# 18-Power-P3V3.net
KiCad netlist of a schematic drawn in Altium Designer
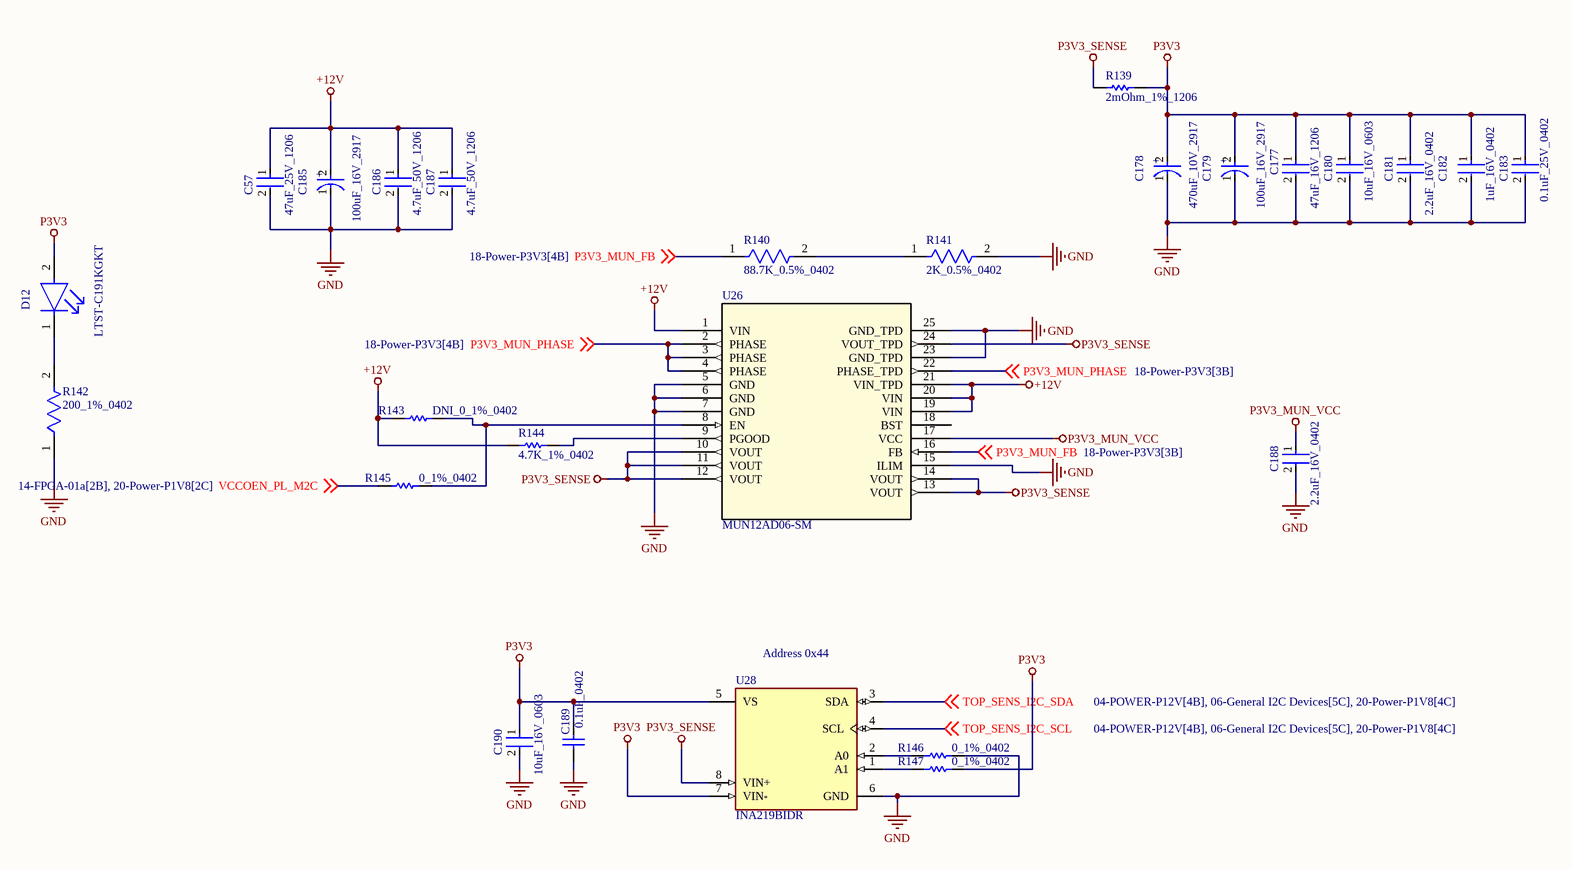
[diagram p0: 18-Power-P3V3.SchDoc]

(export (version "E")
  (design (tool "Eeschema 10.0.6"))
  (components
    (comp (ref "C57")
      (value "47uF_25V_1206")
      (footprint "FP-C3216-160-0_2-MFG")
      (description "Multilayer Ceramic Capacitors 47uF ±20% 25V X5R SMD 1206")
      (fields (field (name "VOLTAGE") "25V") (field (name "TOLERANCE") "20%"))
      (libsource (lib "Altium Content Vault") (part "11868f565c42a9108669ba33697ecf6"))
    )
    (comp (ref "C177")
      (value "47uF_16V_1206")
      (footprint "FP-C3216-160-0_2-MFG")
      (description "Multilayer Ceramic Capacitors 47uF ±20% 16V X5R SMD 1206")
      (fields (field (name "TOLERANCE") "20%"))
      (libsource (lib "Altium Content Vault") (part "11868f565c42a9108669ba33697ecf6"))
    )
    (comp (ref "C178")
      (value "470uF_10V_2917")
      (footprint "FP-TAJE-MFG")
      (description "470uF 10V  ±10% 500mΩ 2917  SMD Tantalum Capacitor")
      (fields (field (name "TOLERANCE") "10%") (field (name "VOLTAGE") "10V"))
      (libsource (lib "Altium Content Vault") (part "203bc49f2ac43e59fd269a8c329ed05"))
    )
    (comp (ref "C179")
      (value "100uF_16V_2917")
      (footprint "FP-T495D107K016ATE125-MFG")
      (description "CAP TANT 100UF 10% 16V 2917")
      (fields (field (name "VOLTAGE") "16V") (field (name "TOLERANCE") "10%"))
      (libsource (lib "Altium Content Vault") (part "a00bbbee19879c290e62620ae7e47b1"))
    )
    (comp (ref "C180")
      (value "10uF_16V_0603")
      (footprint "FP-0603-L_1_6_0_2-W_0_8_0-MFG")
      (description "Multilayer Ceramic Capacitor 10uF 16V X5R 20% SMD 0603 T/R")
      (fields (field (name "TOLERANCE") "20%"))
      (libsource (lib "Altium Content Vault") (part "b4654b650e69147ec39a6b967a45e02"))
    )
    (comp (ref "C181")
      (value "2.2uF_16V_0402")
      (footprint "FP-C1005-050-0_05-IPC_A")
      (description "Multilayer Ceramic Capacitors 2.2μF ±10% 16V X5R SMD 0402")
      (fields (field (name "TOLERANCE") "10%"))
      (libsource (lib "Altium Content Vault") (part "b4654b650e69147ec39a6b967a45e02"))
    )
    (comp (ref "C182")
      (value "1uF_16V_0402")
      (footprint "FP-0402-L_1_0_0_05-W_0_5-IPC_A")
      (description "None")
      (fields (field (name "TOLERANCE") "10%"))
      (libsource (lib "Altium Content Vault") (part "b4654b650e69147ec39a6b967a45e02"))
    )
    (comp (ref "C183")
      (value "0.1uF_25V_0402")
      (footprint "FP-0402-L_1_0_1-W_0_5_0_1-IPC_C")
      (description "General Purpose Ceramic Capacitor, 0402, 100nF, 10%, X7R, 15%, 25V")
      (fields (field (name "VOLTAGE") "25V") (field (name "TOLERANCE") "10%"))
      (libsource (lib "Altium Content Vault") (part "b4654b650e69147ec39a6b967a45e02"))
    )
    (comp (ref "C185")
      (value "100uF_16V_2917")
      (footprint "FP-T495D107K016ATE125-MFG")
      (description "CAP TANT 100UF 10% 16V 2917")
      (fields (field (name "VOLTAGE") "16V") (field (name "TOLERANCE") "10%"))
      (libsource (lib "Altium Content Vault") (part "a00bbbee19879c290e62620ae7e47b1"))
    )
    (comp (ref "C186")
      (value "4.7uF_50V_1206")
      (footprint "FP-GRM31C-0_2-e0_3_0_8-IPC_C")
      (description "Chip Multilayer Ceramic Capacitors for General Purpose, 1206, 4.7uF, X7R, 15%, 10%, 50V")
      (fields (field (name "VOLTAGE") "50V") (field (name "TOLERANCE") "10%"))
      (libsource (lib "Altium Content Vault") (part "02cd4be3c70576c341d710602a673aa"))
    )
    (comp (ref "C187")
      (value "4.7uF_50V_1206")
      (footprint "FP-GRM31C-0_2-e0_3_0_8-IPC_C")
      (description "Chip Multilayer Ceramic Capacitors for General Purpose, 1206, 4.7uF, X7R, 15%, 10%, 50V")
      (fields (field (name "VOLTAGE") "50V") (field (name "TOLERANCE") "10%"))
      (libsource (lib "Altium Content Vault") (part "02cd4be3c70576c341d710602a673aa"))
    )
    (comp (ref "C188")
      (value "2.2uF_16V_0402")
      (footprint "FP-C1005-050-0_05-IPC_A")
      (description "Multilayer Ceramic Capacitors 2.2μF ±10% 16V X5R SMD 0402")
      (fields (field (name "TOLERANCE") "10%"))
      (libsource (lib "Altium Content Vault") (part "b4654b650e69147ec39a6b967a45e02"))
    )
    (comp (ref "C189")
      (value "0.1uF_0402")
      (footprint "CAPC1005X56X25NL10T15")
      (fields
        (field (name "PART NUMBER") "LD02YD104KAB2A")
        (field (name "MANUFACTURER") "AVX Interconnect / Elco")
      )
      (libsource (lib "Altium Content Vault") (part "CAP"))
    )
    (comp (ref "C190")
      (value "10uF_16V_0603")
      (footprint "FP-0603-L_1_6_0_2-W_0_8_0-MFG")
      (description "Multilayer Ceramic Capacitor 10uF 16V X5R 20% SMD 0603 T/R")
      (fields (field (name "TOLERANCE") "20%"))
      (libsource (lib "Altium Content Vault") (part "b4654b650e69147ec39a6b967a45e02"))
    )
    (comp (ref "D12")
      (value "LTST-C191KGKT")
      (footprint "FP-LTST-C191KGKT-MFG")
      (description "LED GREEN CLEAR SMD")
      (libsource (lib "Altium Content Vault") (part "8706943c75ba83719d021d2fdc84c58"))
    )
    (comp (ref "R139")
      (value "2mOhm_1%_1206")
      (footprint "RESC3216X89X64NL25T25")
      (fields (field (name "MANUFACTURER") "Vishay Dale") (field (name "PART NUMBER") "WSL12062L000FEA18"))
      (libsource (lib "Altium Content Vault") (part "RES"))
    )
    (comp (ref "R140")
      (value "88.7K_0.5%_0402")
      (footprint "FP-RT0402-MFG")
      (description "RES SMD 88.7K OHM 0.5% 1/16W")
      (fields
        (field (name "OCTOPART") "https://octopart.com/rt0402dre0788k7l-yageo-1439224")
        (field (name "MANUFACTURER") "Yageo")
      )
      (libsource (lib "Altium Content Vault") (part "1029c3af85768c4190bb7ad29bc67b5"))
    )
    (comp (ref "R141")
      (value "2K_0.5%_0402")
      (footprint "FP-RR0510-IPC_B")
      (description "2kΩ ±0.5% 0.0625W 1/16W Chip Resistor 0402 (1005 Metric) Thin Film")
      (fields (field (name "TOLERANCE") "0.5%"))
      (libsource (lib "Altium Content Vault") (part "1029c3af85768c4190bb7ad29bc67b5"))
    )
    (comp (ref "R142")
      (value "200_1%_0402")
      (footprint "FP-ERJ2RK-IPC_A")
      (description "RES SMD 200 OHM 1% 1/10W 0402")
      (fields (field (name "TOLERANCE") "1%"))
      (libsource (lib "Altium Content Vault") (part "1029c3af85768c4190bb7ad29bc67b5"))
    )
    (comp (ref "R143")
      (value "DNI_0_1%_0402")
      (footprint "RESC1005X40X25LL05T05")
      (description "Chip Resistor, 0 Ohm, 0.1 W, -55 to 155 degC, 0402 (1005 Metric), RoHS, Tape and Reel")
      (fields (field (name "MANUFACTURER") "Panasonic") (field (name "TOLERANCE") "5%"))
      (libsource (lib "Altium Content Vault") (part "RES-2"))
    )
    (comp (ref "R144")
      (value "4.7K_1%_0402")
      (footprint "RESC1005X40X25NL10T10")
      (fields (field (name "MANUFACTURER") "Bourns") (field (name "PART NUMBER") "CR0402-FX-4701GLF"))
      (libsource (lib "Altium Content Vault") (part "RES"))
    )
    (comp (ref "R145")
      (value "0_1%_0402")
      (footprint "RESC1005X40X25LL05T05")
      (description "Chip Resistor, 0 Ohm, 0.1 W, -55 to 155 degC, 0402 (1005 Metric), RoHS, Tape and Reel")
      (fields (field (name "MANUFACTURER") "Panasonic") (field (name "TOLERANCE") "5%"))
      (libsource (lib "Altium Content Vault") (part "RES-2"))
    )
    (comp (ref "R146")
      (value "0_1%_0402")
      (footprint "RESC1005X40X25LL05T05")
      (description "Chip Resistor, 0 Ohm, 0.1 W, -55 to 155 degC, 0402 (1005 Metric), RoHS, Tape and Reel")
      (fields (field (name "MANUFACTURER") "Panasonic") (field (name "TOLERANCE") "5%"))
      (libsource (lib "Altium Content Vault") (part "RES-2"))
    )
    (comp (ref "R147")
      (value "0_1%_0402")
      (footprint "RESC1005X40X25LL05T05")
      (description "Chip Resistor, 0 Ohm, 0.1 W, -55 to 155 degC, 0402 (1005 Metric), RoHS, Tape and Reel")
      (fields (field (name "MANUFACTURER") "Panasonic") (field (name "TOLERANCE") "5%"))
      (libsource (lib "Altium Content Vault") (part "RES-2"))
    )
    (comp (ref "U26")
      (value "MUN12AD06-SM")
      (footprint "MUN12AD06-SM_CYN")
      (description "No Description Available")
      (libsource (lib "MUN12AD06-SM") (part "MUN12AD06-SM"))
    )
    (comp (ref "U28")
      (value "INA219BIDR")
      (footprint "FP-D0008A-MFG")
      (description "IC MONITOR PWR/CURR BIDIR 8-SOIC")
      (libsource (lib "Altium Content Vault") (part "41cc1aee4cbc9fa2660a15773fa0e79"))
    )
  )
  (nets
    (net (code "1") (name "+12V") (class "Default")
      (node (ref "C185") (pin "2") (pinfunction "A_2") (pintype "passive"))
      (node (ref "C186") (pin "1") (pinfunction "1_1") (pintype "passive"))
      (node (ref "C187") (pin "1") (pinfunction "1_1") (pintype "passive"))
      (node (ref "C57") (pin "1") (pinfunction "1_1") (pintype "passive"))
      (node (ref "R143") (pin "1") (pinfunction "1_1") (pintype "passive"))
      (node (ref "R144") (pin "2") (pinfunction "2_2") (pintype "passive"))
      (node (ref "U26") (pin "1") (pinfunction "VIN_1") (pintype "power_in"))
      (node (ref "U26") (pin "19") (pinfunction "VIN_19") (pintype "power_in"))
      (node (ref "U26") (pin "20") (pinfunction "VIN_20") (pintype "power_in"))
      (node (ref "U26") (pin "21") (pinfunction "VIN_TPD_21") (pintype "power_in"))
    )
    (net (code "2") (name "GND") (class "Default")
      (node (ref "C177") (pin "2") (pinfunction "2_2") (pintype "passive"))
      (node (ref "C178") (pin "1") (pinfunction "C_1") (pintype "passive"))
      (node (ref "C179") (pin "1") (pinfunction "C_1") (pintype "passive"))
      (node (ref "C180") (pin "2") (pinfunction "2_2") (pintype "passive"))
      (node (ref "C181") (pin "2") (pinfunction "2_2") (pintype "passive"))
      (node (ref "C182") (pin "2") (pinfunction "2_2") (pintype "passive"))
      (node (ref "C183") (pin "2") (pinfunction "2_2") (pintype "passive"))
      (node (ref "C185") (pin "1") (pinfunction "C_1") (pintype "passive"))
      (node (ref "C186") (pin "2") (pinfunction "2_2") (pintype "passive"))
      (node (ref "C187") (pin "2") (pinfunction "2_2") (pintype "passive"))
      (node (ref "C188") (pin "2") (pinfunction "2_2") (pintype "passive"))
      (node (ref "C189") (pin "1") (pinfunction "1_1") (pintype "passive"))
      (node (ref "C190") (pin "2") (pinfunction "2_2") (pintype "passive"))
      (node (ref "C57") (pin "2") (pinfunction "2_2") (pintype "passive"))
      (node (ref "R141") (pin "2") (pinfunction "2_2") (pintype "passive"))
      (node (ref "R142") (pin "1") (pinfunction "1_1") (pintype "passive"))
      (node (ref "R146") (pin "2") (pinfunction "2_2") (pintype "passive"))
      (node (ref "U26") (pin "15") (pinfunction "ILIM_15") (pintype "passive"))
      (node (ref "U26") (pin "23") (pinfunction "GND_TPD_23") (pintype "power_in"))
      (node (ref "U26") (pin "25") (pinfunction "GND_TPD_25") (pintype "power_in"))
      (node (ref "U26") (pin "5") (pinfunction "GND_5") (pintype "power_in"))
      (node (ref "U26") (pin "6") (pinfunction "GND_6") (pintype "power_in"))
      (node (ref "U26") (pin "7") (pinfunction "GND_7") (pintype "power_in"))
      (node (ref "U28") (pin "6") (pinfunction "GND_6") (pintype "power_in"))
    )
    (net (code "3") (name "Net-(D12-C)") (class "Default")
      (node (ref "D12") (pin "1") (pinfunction "C_1") (pintype "passive"))
      (node (ref "R142") (pin "2") (pinfunction "2_2") (pintype "passive"))
    )
    (net (code "4") (name "Net-(R140-Pad2)") (class "Default")
      (node (ref "R140") (pin "2") (pinfunction "2_2") (pintype "passive"))
      (node (ref "R141") (pin "1") (pinfunction "1_1") (pintype "passive"))
    )
    (net (code "5") (name "Net-(U26-EN)") (class "Default")
      (node (ref "R143") (pin "2") (pinfunction "2_2") (pintype "passive"))
      (node (ref "R145") (pin "2") (pinfunction "2_2") (pintype "passive"))
      (node (ref "U26") (pin "8") (pinfunction "EN_8") (pintype "input"))
    )
    (net (code "6") (name "Net-(U26-PGOOD)") (class "Default")
      (node (ref "R144") (pin "1") (pinfunction "1_1") (pintype "passive"))
      (node (ref "U26") (pin "9") (pinfunction "PGOOD_9") (pintype "output"))
    )
    (net (code "7") (name "Net-(U28-A0)") (class "Default")
      (node (ref "R146") (pin "1") (pinfunction "1_1") (pintype "passive"))
      (node (ref "U28") (pin "2") (pinfunction "A0_2") (pintype "input"))
    )
    (net (code "8") (name "Net-(U28-A1)") (class "Default")
      (node (ref "R147") (pin "1") (pinfunction "1_1") (pintype "passive"))
      (node (ref "U28") (pin "1") (pinfunction "A1_1") (pintype "input"))
    )
    (net (code "9") (name "P3V3") (class "Default")
      (node (ref "C177") (pin "1") (pinfunction "1_1") (pintype "passive"))
      (node (ref "C178") (pin "2") (pinfunction "A_2") (pintype "passive"))
      (node (ref "C179") (pin "2") (pinfunction "A_2") (pintype "passive"))
      (node (ref "C180") (pin "1") (pinfunction "1_1") (pintype "passive"))
      (node (ref "C181") (pin "1") (pinfunction "1_1") (pintype "passive"))
      (node (ref "C182") (pin "1") (pinfunction "1_1") (pintype "passive"))
      (node (ref "C183") (pin "1") (pinfunction "1_1") (pintype "passive"))
      (node (ref "C189") (pin "2") (pinfunction "2_2") (pintype "passive"))
      (node (ref "C190") (pin "1") (pinfunction "1_1") (pintype "passive"))
      (node (ref "D12") (pin "2") (pinfunction "A_2") (pintype "passive"))
      (node (ref "R139") (pin "2") (pinfunction "2_2") (pintype "passive"))
      (node (ref "R147") (pin "2") (pinfunction "2_2") (pintype "passive"))
      (node (ref "U28") (pin "5") (pinfunction "VS_5") (pintype "power_in"))
      (node (ref "U28") (pin "7") (pinfunction "VIN-_7") (pintype "input"))
    )
    (net (code "10") (name "P3V3_MUN_FB") (class "Default")
      (node (ref "R140") (pin "1") (pinfunction "1_1") (pintype "passive"))
      (node (ref "U26") (pin "16") (pinfunction "FB_16") (pintype "input"))
    )
    (net (code "11") (name "P3V3_MUN_PHASE") (class "Default")
      (node (ref "U26") (pin "2") (pinfunction "PHASE_2") (pintype "output"))
      (node (ref "U26") (pin "22") (pinfunction "PHASE_TPD_22") (pintype "output"))
      (node (ref "U26") (pin "3") (pinfunction "PHASE_3") (pintype "output"))
      (node (ref "U26") (pin "4") (pinfunction "PHASE_4") (pintype "output"))
    )
    (net (code "12") (name "P3V3_MUN_VCC") (class "Default")
      (node (ref "C188") (pin "1") (pinfunction "1_1") (pintype "passive"))
      (node (ref "U26") (pin "17") (pinfunction "VCC_17") (pintype "power_in"))
    )
    (net (code "13") (name "P3V3_SENSE") (class "Default")
      (node (ref "R139") (pin "1") (pinfunction "1_1") (pintype "passive"))
      (node (ref "U26") (pin "10") (pinfunction "VOUT_10") (pintype "output"))
      (node (ref "U26") (pin "11") (pinfunction "VOUT_11") (pintype "output"))
      (node (ref "U26") (pin "12") (pinfunction "VOUT_12") (pintype "output"))
      (node (ref "U26") (pin "13") (pinfunction "VOUT_13") (pintype "output"))
      (node (ref "U26") (pin "14") (pinfunction "VOUT_14") (pintype "output"))
      (node (ref "U26") (pin "24") (pinfunction "VOUT_TPD_24") (pintype "output"))
      (node (ref "U28") (pin "8") (pinfunction "VIN+_8") (pintype "input"))
    )
    (net (code "14") (name "TOP_SENS_I2C_SCL") (class "Default")
      (node (ref "U28") (pin "4") (pinfunction "SCL_4") (pintype "bidirectional"))
    )
    (net (code "15") (name "TOP_SENS_I2C_SDA") (class "Default")
      (node (ref "U28") (pin "3") (pinfunction "SDA_3") (pintype "bidirectional"))
    )
    (net (code "16") (name "VCCOEN_PL_M2C") (class "Default")
      (node (ref "R145") (pin "1") (pinfunction "1_1") (pintype "passive"))
    )
    (net (code "17") (name "unconnected-(U26-BST-Pad18)") (class "Default")
      (node (ref "U26") (pin "18") (pinfunction "BST_18") (pintype "power_in"))
    )
  )
)
